# brush_driver.net
KiCad netlist of a schematic drawn in Altium Designer
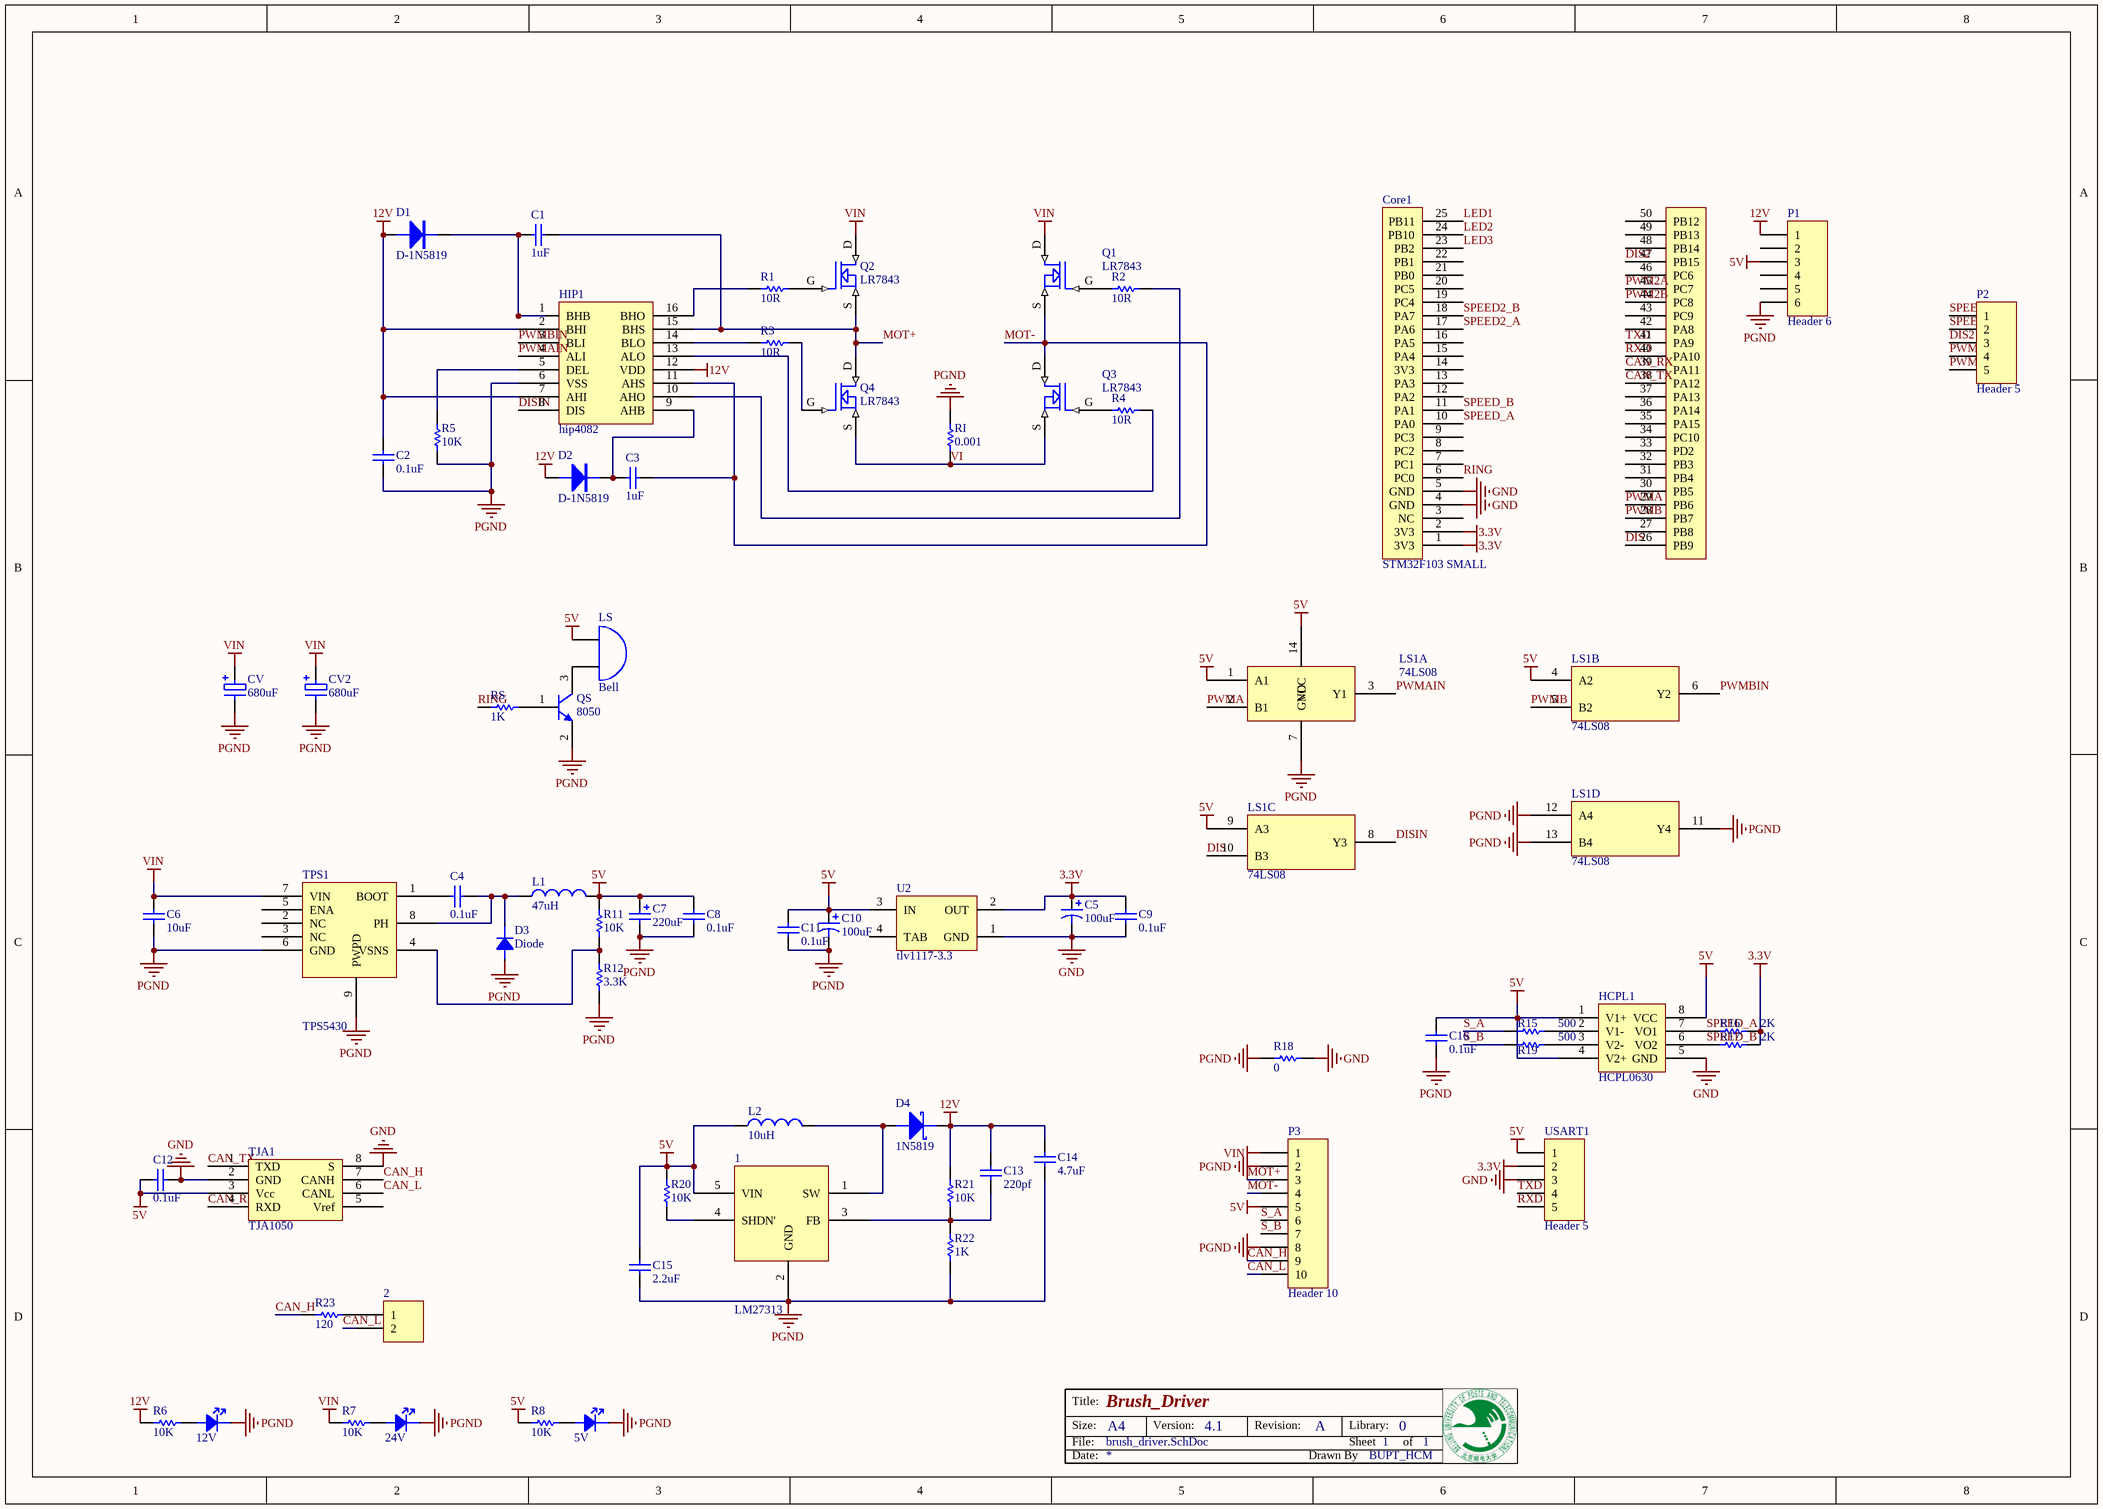
[diagram p0: brush_driver.SchDoc]

(export (version "E")
  (design (tool "Eeschema 10.0.6"))
  (components
    (comp (ref "1")
      (value "LM27313")
      (footprint "LM27313")
      (libsource (lib "K60-mainboard-v3.1") (part "LM27313"))
    )
    (comp (ref "2")
      (value "Header 2")
      (footprint "SIP2")
      (description "Header, 2-Pin")
      (fields (field (name "PUBLISHER") "Altium Limited"))
      (libsource (lib "Libraries_2014_0618") (part "Header 2"))
    )
    (comp (ref "5V")
      (value "lED")
      (footprint "0805D")
      (description "LED")
      (libsource (lib "K60-mainboard-v3.1") (part "00-D-LED"))
    )
    (comp (ref "12V")
      (value "lED")
      (footprint "0805D")
      (description "LED")
      (libsource (lib "K60-mainboard-v3.1") (part "00-D-LED"))
    )
    (comp (ref "24V")
      (value "lED")
      (footprint "0805D")
      (description "LED")
      (libsource (lib "K60-mainboard-v3.1") (part "00-D-LED"))
    )
    (comp (ref "C1")
      (value "1uF")
      (footprint "CAP-MLCC-0603")
      (description "Capacitor")
      (fields (field (name "Comment") "Cap") (field (name "PUBLISHER") "Altium Limited"))
      (libsource (lib "K60-mainboard-v3.1") (part "Cap"))
    )
    (comp (ref "C2")
      (value "0.1uF")
      (footprint "CAP-MLCC-0603")
      (description "Capacitor")
      (fields (field (name "Comment") "Cap") (field (name "PUBLISHER") "Altium Limited"))
      (libsource (lib "K60-mainboard-v3.1") (part "Cap"))
    )
    (comp (ref "C3")
      (value "1uF")
      (footprint "CAP-MLCC-0603")
      (description "Capacitor")
      (fields (field (name "Comment") "Cap") (field (name "PUBLISHER") "Altium Limited"))
      (libsource (lib "K60-mainboard-v3.1") (part "Cap"))
    )
    (comp (ref "C4")
      (value "0.1uF")
      (footprint "CAP-MLCC-0603")
      (description "Capacitor")
      (fields (field (name "Comment") "Cap") (field (name "PUBLISHER") "Altium Limited"))
      (libsource (lib "K60-mainboard-v3.1") (part "Cap"))
    )
    (comp (ref "C5")
      (value "100uF")
      (footprint "6032C")
      (description "Polarized Capacitor (Surface Mount)")
      (fields (field (name "Comment") "Cap Pol3") (field (name "PUBLISHER") "Altium Limited"))
      (libsource (lib "K60-mainboard-v3.1") (part "Cap Pol3"))
    )
    (comp (ref "C6")
      (value "10uF")
      (footprint "0805C")
      (description "Capacitor")
      (fields (field (name "Comment") "Cap") (field (name "PUBLISHER") "Altium Limited"))
      (libsource (lib "K60-mainboard-v3.1") (part "Cap"))
    )
    (comp (ref "C7")
      (value "220uF")
      (footprint "CAP-TAN-7343/CAPD")
      (description "Polarized Capacitor (Radial)")
      (fields (field (name "Comment") "Cap Pol1") (field (name "PUBLISHER") "Altium Limited"))
      (libsource (lib "K60-mainboard-v3.1") (part "Cap Pol1"))
    )
    (comp (ref "C8")
      (value "0.1uF")
      (footprint "CAP-MLCC-0603")
      (description "Capacitor")
      (fields (field (name "Comment") "Cap") (field (name "PUBLISHER") "Altium Limited"))
      (libsource (lib "K60-mainboard-v3.1") (part "Cap"))
    )
    (comp (ref "C9")
      (value "0.1uF")
      (footprint "CAP-MLCC-0603")
      (description "Capacitor")
      (fields (field (name "Comment") "Cap") (field (name "PUBLISHER") "Altium Limited"))
      (libsource (lib "K60-mainboard-v3.1") (part "Cap"))
    )
    (comp (ref "C10")
      (value "100uF")
      (footprint "6032C")
      (description "Polarized Capacitor (Surface Mount)")
      (fields (field (name "Comment") "Cap Pol3") (field (name "PUBLISHER") "Altium Limited"))
      (libsource (lib "K60-mainboard-v3.1") (part "Cap Pol3"))
    )
    (comp (ref "C11")
      (value "0.1uF")
      (footprint "CAP-MLCC-0603")
      (description "Capacitor")
      (fields (field (name "Comment") "Cap") (field (name "PUBLISHER") "Altium Limited"))
      (libsource (lib "K60-mainboard-v3.1") (part "Cap"))
    )
    (comp (ref "C12")
      (value "0.1uF")
      (footprint "CAP-MLCC-0603")
      (description "Capacitor")
      (fields (field (name "Comment") "Cap") (field (name "PUBLISHER") "Altium Limited"))
      (libsource (lib "K60-mainboard-v3.1") (part "Cap"))
    )
    (comp (ref "C13")
      (value "220pf")
      (footprint "CAP-MLCC-0603")
      (description "Capacitor")
      (fields (field (name "Comment") "Cap") (field (name "PUBLISHER") "Altium Limited"))
      (libsource (lib "K60-mainboard-v3.1") (part "Cap_1"))
    )
    (comp (ref "C14")
      (value "4.7uF")
      (footprint "CAP-MLCC-0603")
      (description "Capacitor")
      (fields (field (name "Comment") "Cap") (field (name "PUBLISHER") "Altium Limited"))
      (libsource (lib "K60-mainboard-v3.1") (part "Cap_1"))
    )
    (comp (ref "C15")
      (value "2.2uF")
      (footprint "CAP-MLCC-0603")
      (description "Capacitor")
      (fields (field (name "Comment") "Cap") (field (name "PUBLISHER") "Altium Limited"))
      (libsource (lib "K60-mainboard-v3.1") (part "Cap_1"))
    )
    (comp (ref "C16")
      (value "0.1uF")
      (footprint "CAP-MLCC-0603")
      (description "Capacitor")
      (fields (field (name "Comment") "Cap") (field (name "PUBLISHER") "Altium Limited"))
      (libsource (lib "K60-mainboard-v3.1") (part "Cap"))
    )
    (comp (ref "Core1")
      (value "STM32F103 SMALL")
      (footprint "STM32F103Small")
      (libsource (lib "K60-mainboard-v3.1") (part "STM32F103 SMALL"))
    )
    (comp (ref "CV")
      (value "680uF")
      (footprint "C_ELE")
      (description "电解电容")
      (fields (field (name "PUBLISHER") "Altium Limited"))
      (libsource (lib "Libraries_2014_0618") (part "CAP-ELE"))
    )
    (comp (ref "CV2")
      (value "680uF")
      (footprint "C_ELE")
      (description "电解电容")
      (fields (field (name "PUBLISHER") "Altium Limited"))
      (libsource (lib "Libraries_2014_0618") (part "CAP-ELE"))
    )
    (comp (ref "D1")
      (value "D-1N5819")
      (footprint "0805D")
      (description "Diode")
      (libsource (lib "常用器件") (part "D-1N5819"))
    )
    (comp (ref "D2")
      (value "D-1N5819")
      (footprint "0805D")
      (description "Diode")
      (libsource (lib "常用器件") (part "D-1N5819"))
    )
    (comp (ref "D3") (value "Diode") (footprint "SS34") (libsource (lib "K60-mainboard-v3.1") (part "Diode")))
    (comp (ref "D4")
      (value "1N5819")
      (footprint "0805D")
      (description "MBRA140T3")
      (libsource (lib "常用器件") (part "D-MBRA140T3"))
    )
    (comp (ref "HCPL1")
      (value "HCPL0630")
      (footprint "SOIC8")
      (libsource (lib "K60-mainboard-v3.1") (part "HCPL0630"))
    )
    (comp (ref "HIP1") (value "hip4082") (footprint "SOP16") (libsource (lib "元件库") (part "hip4082")))
    (comp (ref "L1")
      (value "47uH")
      (footprint "CD74")
      (description "Inductor")
      (fields (field (name "PUBLISHER") "Altium Limited"))
      (libsource (lib "smartcar_example") (part "Inductor"))
    )
    (comp (ref "L2")
      (value "10uH")
      (footprint "CD52")
      (description "Inductor")
      (fields (field (name "PUBLISHER") "Altium Limited"))
      (libsource (lib "smartcar_example") (part "Inductor"))
    )
    (comp (ref "LS")
      (value "Bell")
      (footprint "Ring")
      (description "Electrical Bell")
      (fields (field (name "PUBLISHER") "Altium Limited"))
      (libsource (lib "附加元件") (part "Bell"))
    )
    (comp (ref "LS1")
      (value "74LS08")
      (footprint "SOJ-14")
      (libsource (lib "K60-mainboard-v3.1") (part "74LS08"))
    )
    (comp (ref "P1")
      (value "Header 6")
      (footprint "HDR1X6")
      (description "Header, 6-Pin")
      (fields (field (name "PUBLISHER") "Altium Limited"))
      (libsource (lib "K60-mainboard-v3.1") (part "Header 6"))
    )
    (comp (ref "P2")
      (value "Header 5")
      (footprint "HDR1X5")
      (description "Header, 5-Pin")
      (fields (field (name "PUBLISHER") "Altium Limited"))
      (libsource (lib "K60-mainboard-v3.1") (part "Header 5"))
    )
    (comp (ref "P3")
      (value "Header 10")
      (footprint "Green 10P")
      (description "Header, 10-Pin")
      (fields (field (name "PUBLISHER") "Altium Limited"))
      (libsource (lib "Libraries_2014_0618") (part "Header 10"))
    )
    (comp (ref "Q1")
      (value "LR7843")
      (footprint "LR7843")
      (libsource (lib "K60-mainboard-v3.1") (part "LR7843"))
    )
    (comp (ref "Q2")
      (value "LR7843")
      (footprint "LR7843")
      (libsource (lib "K60-mainboard-v3.1") (part "LR7843"))
    )
    (comp (ref "Q3")
      (value "LR7843")
      (footprint "LR7843")
      (libsource (lib "K60-mainboard-v3.1") (part "LR7843"))
    )
    (comp (ref "Q4")
      (value "LR7843")
      (footprint "LR7843")
      (libsource (lib "K60-mainboard-v3.1") (part "LR7843"))
    )
    (comp (ref "QS")
      (value "8050")
      (footprint "SOT-23B_N")
      (description "NPN Bipolar Transistor")
      (fields (field (name "PUBLISHER") "Altium Limited"))
      (libsource (lib "附加元件") (part "QNPN"))
    )
    (comp (ref "R1")
      (value "10R")
      (footprint "RES-0603")
      (description "Resistor")
      (fields (field (name "Comment") "Res1") (field (name "PUBLISHER") "Altium Limited"))
      (libsource (lib "K60-mainboard-v3.1") (part "Res1"))
    )
    (comp (ref "R2")
      (value "10R")
      (footprint "RES-0603")
      (description "Resistor")
      (fields (field (name "Comment") "Res1") (field (name "PUBLISHER") "Altium Limited"))
      (libsource (lib "K60-mainboard-v3.1") (part "Res1"))
    )
    (comp (ref "R3")
      (value "10R")
      (footprint "RES-0603")
      (description "Resistor")
      (fields (field (name "Comment") "Res1") (field (name "PUBLISHER") "Altium Limited"))
      (libsource (lib "K60-mainboard-v3.1") (part "Res1"))
    )
    (comp (ref "R4")
      (value "10R")
      (footprint "RES-0603")
      (description "Resistor")
      (fields (field (name "Comment") "Res1") (field (name "PUBLISHER") "Altium Limited"))
      (libsource (lib "K60-mainboard-v3.1") (part "Res1"))
    )
    (comp (ref "R5")
      (value "10K")
      (footprint "RES-0603")
      (description "Resistor")
      (fields (field (name "Comment") "Res1") (field (name "PUBLISHER") "Altium Limited"))
      (libsource (lib "K60-mainboard-v3.1") (part "Res1"))
    )
    (comp (ref "R6")
      (value "10K")
      (footprint "RES-0603")
      (description "Resistor")
      (fields (field (name "Comment") "Res1") (field (name "PUBLISHER") "Altium Limited"))
      (libsource (lib "K60-mainboard-v3.1") (part "Res1"))
    )
    (comp (ref "R7")
      (value "10K")
      (footprint "RES-0603")
      (description "Resistor")
      (fields (field (name "Comment") "Res1") (field (name "PUBLISHER") "Altium Limited"))
      (libsource (lib "K60-mainboard-v3.1") (part "Res1"))
    )
    (comp (ref "R8")
      (value "10K")
      (footprint "RES-0603")
      (description "Resistor")
      (fields (field (name "Comment") "Res1") (field (name "PUBLISHER") "Altium Limited"))
      (libsource (lib "K60-mainboard-v3.1") (part "Res1"))
    )
    (comp (ref "R11")
      (value "10K")
      (footprint "RES-0603")
      (description "Resistor")
      (fields (field (name "Comment") "Res1") (field (name "PUBLISHER") "Altium Limited"))
      (libsource (lib "K60-mainboard-v3.1") (part "Res1"))
    )
    (comp (ref "R12")
      (value "3.3K")
      (footprint "RES-0603")
      (description "Resistor")
      (fields (field (name "Comment") "Res1") (field (name "PUBLISHER") "Altium Limited"))
      (libsource (lib "K60-mainboard-v3.1") (part "Res1"))
    )
    (comp (ref "R15")
      (value "500")
      (footprint "RES-0603")
      (description "Resistor")
      (fields (field (name "Comment") "Res1") (field (name "PUBLISHER") "Altium Limited"))
      (libsource (lib "K60-mainboard-v3.1") (part "Res1"))
    )
    (comp (ref "R16")
      (value "2K")
      (footprint "RES-0603")
      (description "Resistor")
      (fields (field (name "Comment") "Res1") (field (name "PUBLISHER") "Altium Limited"))
      (libsource (lib "K60-mainboard-v3.1") (part "Res1"))
    )
    (comp (ref "R17")
      (value "2K")
      (footprint "RES-0603")
      (description "Resistor")
      (fields (field (name "Comment") "Res1") (field (name "PUBLISHER") "Altium Limited"))
      (libsource (lib "K60-mainboard-v3.1") (part "Res1"))
    )
    (comp (ref "R18")
      (value "0")
      (footprint "RES-0603")
      (description "Resistor")
      (fields (field (name "Comment") "Res1") (field (name "PUBLISHER") "Altium Limited"))
      (libsource (lib "K60-mainboard-v3.1") (part "Res1"))
    )
    (comp (ref "R19")
      (value "500")
      (footprint "RES-0603")
      (description "Resistor")
      (fields (field (name "Comment") "Res1") (field (name "PUBLISHER") "Altium Limited"))
      (libsource (lib "K60-mainboard-v3.1") (part "Res1"))
    )
    (comp (ref "R20")
      (value "10K")
      (footprint "RES-0603")
      (description "Resistor")
      (fields (field (name "Comment") "Res1") (field (name "PUBLISHER") "Altium Limited"))
      (libsource (lib "K60-mainboard-v3.1") (part "Res1_1"))
    )
    (comp (ref "R21")
      (value "10K")
      (footprint "RES-0603")
      (description "Resistor")
      (fields (field (name "Comment") "Res1") (field (name "PUBLISHER") "Altium Limited"))
      (libsource (lib "K60-mainboard-v3.1") (part "Res1_1"))
    )
    (comp (ref "R22")
      (value "1K")
      (footprint "RES-0603")
      (description "Resistor")
      (fields (field (name "Comment") "Res1") (field (name "PUBLISHER") "Altium Limited"))
      (libsource (lib "K60-mainboard-v3.1") (part "Res1_1"))
    )
    (comp (ref "R23")
      (value "120")
      (footprint "RES-0603")
      (description "Resistor")
      (fields (field (name "Comment") "Res1") (field (name "PUBLISHER") "Altium Limited"))
      (libsource (lib "K60-mainboard-v3.1") (part "Res1"))
    )
    (comp (ref "RI")
      (value "0.001")
      (footprint "2512R")
      (description "Resistor")
      (fields (field (name "Comment") "Res1") (field (name "PUBLISHER") "Altium Limited"))
      (libsource (lib "K60-mainboard-v3.1") (part "Res1"))
    )
    (comp (ref "RS")
      (value "1K")
      (footprint "RES-0603")
      (description "Resistor")
      (fields (field (name "Comment") "Res1") (field (name "PUBLISHER") "Altium Limited"))
      (libsource (lib "K60-mainboard-v3.1") (part "Res1"))
    )
    (comp (ref "TJA1")
      (value "TJA1050")
      (footprint "TJA1050")
      (description "CAN总线收发器")
      (libsource (lib "Libraries_2014_0618") (part "TJA1050"))
    )
    (comp (ref "TPS1")
      (value "TPS5430")
      (footprint "TPS5430")
      (libsource (lib "K60-mainboard-v3.1") (part "TPS5430"))
    )
    (comp (ref "U2")
      (value "tlv1117-3.3")
      (footprint "LM1117")
      (description "800mA Low-Dropout Linear Regulator")
      (fields
        (field (name "PARTNUMBER") "LM1117IMP-5.0")
        (field (name "MANUFACTURER") "National Semiconductor")
        (field (name "PUBLISHER") "Altium Limited")
      )
      (libsource (lib "K60-mainboard-v3.1") (part "LM1117IMP-5.0"))
    )
    (comp (ref "USART1")
      (value "Header 5")
      (footprint "Green_5P")
      (description "Header, 5-Pin")
      (fields (field (name "PUBLISHER") "Altium Limited"))
      (libsource (lib "Libraries_2014_0618") (part "Header 5"))
    )
  )
  (nets
    (net (code "1") (name "/CAN_H") (class "Default")
      (node (ref "P3") (pin "9") (pinfunction "9_9") (pintype "passive"))
      (node (ref "R23") (pin "2") (pinfunction "2_2") (pintype "passive"))
      (node (ref "TJA1") (pin "7") (pinfunction "CANH_7") (pintype "passive"))
    )
    (net (code "2") (name "/CAN_L") (class "Default")
      (node (ref "2") (pin "2") (pinfunction "2_2") (pintype "passive"))
      (node (ref "P3") (pin "10") (pinfunction "10_10") (pintype "passive"))
      (node (ref "TJA1") (pin "6") (pinfunction "CANL_6") (pintype "passive"))
    )
    (net (code "3") (name "/CAN_RX") (class "Default")
      (node (ref "Core1") (pin "39") (pinfunction "PA11_39") (pintype "passive"))
      (node (ref "TJA1") (pin "4") (pinfunction "RXD_4") (pintype "passive"))
    )
    (net (code "4") (name "/CAN_TX") (class "Default")
      (node (ref "Core1") (pin "38") (pinfunction "PA12_38") (pintype "passive"))
      (node (ref "TJA1") (pin "1") (pinfunction "TXD_1") (pintype "passive"))
    )
    (net (code "5") (name "/DIS") (class "Default")
      (node (ref "Core1") (pin "26") (pinfunction "PB9_26") (pintype "passive"))
      (node (ref "LS1") (pin "10") (pinfunction "B3_10") (pintype "passive"))
    )
    (net (code "6") (name "/DIS2") (class "Default")
      (node (ref "Core1") (pin "47") (pinfunction "PB15_47") (pintype "passive"))
      (node (ref "P2") (pin "3") (pinfunction "3_3") (pintype "passive"))
    )
    (net (code "7") (name "/DISIN") (class "Default")
      (node (ref "HIP1") (pin "8") (pinfunction "DIS_8") (pintype "passive"))
      (node (ref "LS1") (pin "8") (pinfunction "Y3_8") (pintype "passive"))
    )
    (net (code "8") (name "/LED1") (class "Default")
      (node (ref "Core1") (pin "25") (pinfunction "PB11_25") (pintype "passive"))
    )
    (net (code "9") (name "/LED2") (class "Default")
      (node (ref "Core1") (pin "24") (pinfunction "PB10_24") (pintype "passive"))
    )
    (net (code "10") (name "/LED3") (class "Default")
      (node (ref "Core1") (pin "23") (pinfunction "PB2_23") (pintype "passive"))
    )
    (net (code "11") (name "/MOT+") (class "Default")
      (node (ref "C1") (pin "1") (pinfunction "1_1") (pintype "passive"))
      (node (ref "HIP1") (pin "15") (pinfunction "BHS_15") (pintype "passive"))
      (node (ref "P3") (pin "3") (pinfunction "3_3") (pintype "passive"))
      (node (ref "Q2") (pin "S") (pinfunction "S_S") (pintype "input"))
      (node (ref "Q4") (pin "D") (pinfunction "D_D") (pintype "input"))
    )
    (net (code "12") (name "/MOT-") (class "Default")
      (node (ref "C3") (pin "1") (pinfunction "1_1") (pintype "passive"))
      (node (ref "HIP1") (pin "11") (pinfunction "AHS_11") (pintype "passive"))
      (node (ref "P3") (pin "4") (pinfunction "4_4") (pintype "passive"))
      (node (ref "Q1") (pin "S") (pinfunction "S_S") (pintype "input"))
      (node (ref "Q3") (pin "D") (pinfunction "D_D") (pintype "input"))
    )
    (net (code "13") (name "/PWM2A") (class "Default")
      (node (ref "Core1") (pin "45") (pinfunction "PC7_45") (pintype "passive"))
      (node (ref "P2") (pin "4") (pinfunction "4_4") (pintype "passive"))
    )
    (net (code "14") (name "/PWM2B") (class "Default")
      (node (ref "Core1") (pin "44") (pinfunction "PC8_44") (pintype "passive"))
      (node (ref "P2") (pin "5") (pinfunction "5_5") (pintype "passive"))
    )
    (net (code "15") (name "/PWMA") (class "Default")
      (node (ref "Core1") (pin "29") (pinfunction "PB6_29") (pintype "passive"))
      (node (ref "LS1") (pin "2") (pinfunction "B1_2") (pintype "passive"))
    )
    (net (code "16") (name "/PWMAIN") (class "Default")
      (node (ref "HIP1") (pin "4") (pinfunction "ALI_4") (pintype "passive"))
      (node (ref "LS1") (pin "3") (pinfunction "Y1_3") (pintype "passive"))
    )
    (net (code "17") (name "/PWMB") (class "Default")
      (node (ref "Core1") (pin "28") (pinfunction "PB7_28") (pintype "passive"))
      (node (ref "LS1") (pin "5") (pinfunction "B2_5") (pintype "passive"))
    )
    (net (code "18") (name "/PWMBIN") (class "Default")
      (node (ref "HIP1") (pin "3") (pinfunction "BLI_3") (pintype "passive"))
      (node (ref "LS1") (pin "6") (pinfunction "Y2_6") (pintype "passive"))
    )
    (net (code "19") (name "/RING") (class "Default")
      (node (ref "Core1") (pin "6") (pinfunction "PC0_6") (pintype "passive"))
      (node (ref "RS") (pin "2") (pinfunction "2_2") (pintype "passive"))
    )
    (net (code "20") (name "/RXD") (class "Default")
      (node (ref "Core1") (pin "40") (pinfunction "PA10_40") (pintype "passive"))
      (node (ref "USART1") (pin "5") (pinfunction "5_5") (pintype "passive"))
    )
    (net (code "21") (name "/SPEED2_A") (class "Default")
      (node (ref "Core1") (pin "17") (pinfunction "PA6_17") (pintype "passive"))
      (node (ref "P2") (pin "2") (pinfunction "2_2") (pintype "passive"))
    )
    (net (code "22") (name "/SPEED2_B") (class "Default")
      (node (ref "Core1") (pin "18") (pinfunction "PA7_18") (pintype "passive"))
      (node (ref "P2") (pin "1") (pinfunction "1_1") (pintype "passive"))
    )
    (net (code "23") (name "/SPEED_A") (class "Default")
      (node (ref "Core1") (pin "10") (pinfunction "PA0_10") (pintype "passive"))
      (node (ref "HCPL1") (pin "7") (pinfunction "VO1_7") (pintype "passive"))
      (node (ref "R16") (pin "1") (pinfunction "1_1") (pintype "passive"))
    )
    (net (code "24") (name "/SPEED_B") (class "Default")
      (node (ref "Core1") (pin "11") (pinfunction "PA1_11") (pintype "passive"))
      (node (ref "HCPL1") (pin "6") (pinfunction "VO2_6") (pintype "passive"))
      (node (ref "R17") (pin "1") (pinfunction "1_1") (pintype "passive"))
    )
    (net (code "25") (name "/S_A") (class "Default")
      (node (ref "P3") (pin "6") (pinfunction "6_6") (pintype "passive"))
      (node (ref "R15") (pin "1") (pinfunction "1_1") (pintype "passive"))
    )
    (net (code "26") (name "/S_B") (class "Default")
      (node (ref "P3") (pin "7") (pinfunction "7_7") (pintype "passive"))
      (node (ref "R19") (pin "1") (pinfunction "1_1") (pintype "passive"))
    )
    (net (code "27") (name "/TXD") (class "Default")
      (node (ref "Core1") (pin "41") (pinfunction "PA9_41") (pintype "passive"))
      (node (ref "USART1") (pin "4") (pinfunction "4_4") (pintype "passive"))
    )
    (net (code "28") (name "/VI") (class "Default")
      (node (ref "Q3") (pin "S") (pinfunction "S_S") (pintype "input"))
      (node (ref "Q4") (pin "S") (pinfunction "S_S") (pintype "input"))
      (node (ref "RI") (pin "1") (pinfunction "1_1") (pintype "passive"))
    )
    (net (code "29") (name "3.3V") (class "Default")
      (node (ref "C5") (pin "1") (pinfunction "1_1") (pintype "passive"))
      (node (ref "C9") (pin "1") (pinfunction "1_1") (pintype "passive"))
      (node (ref "Core1") (pin "1") (pinfunction "3V3_1") (pintype "passive"))
      (node (ref "Core1") (pin "2") (pinfunction "3V3_2") (pintype "passive"))
      (node (ref "R16") (pin "2") (pinfunction "2_2") (pintype "passive"))
      (node (ref "R17") (pin "2") (pinfunction "2_2") (pintype "passive"))
      (node (ref "U2") (pin "2") (pinfunction "OUT_2") (pintype "power_in"))
      (node (ref "USART1") (pin "2") (pinfunction "2_2") (pintype "passive"))
    )
    (net (code "30") (name "5V") (class "Default")
      (node (ref "1") (pin "5") (pinfunction "VIN_5") (pintype "passive"))
      (node (ref "C10") (pin "1") (pinfunction "1_1") (pintype "passive"))
      (node (ref "C11") (pin "1") (pinfunction "1_1") (pintype "passive"))
      (node (ref "C12") (pin "1") (pinfunction "1_1") (pintype "passive"))
      (node (ref "C15") (pin "2") (pinfunction "2_2") (pintype "passive"))
      (node (ref "C16") (pin "1") (pinfunction "1_1") (pintype "passive"))
      (node (ref "C7") (pin "1") (pinfunction "1_1") (pintype "passive"))
      (node (ref "C8") (pin "2") (pinfunction "2_2") (pintype "passive"))
      (node (ref "HCPL1") (pin "1") (pinfunction "V1+_1") (pintype "passive"))
      (node (ref "HCPL1") (pin "4") (pinfunction "V2+_4") (pintype "passive"))
      (node (ref "HCPL1") (pin "8") (pinfunction "VCC_8") (pintype "passive"))
      (node (ref "L1") (pin "2") (pinfunction "2_2") (pintype "passive"))
      (node (ref "L2") (pin "1") (pinfunction "1_1") (pintype "passive"))
      (node (ref "LS") (pin "1") (pinfunction "A_1") (pintype "passive"))
      (node (ref "LS1") (pin "1") (pinfunction "A1_1") (pintype "passive"))
      (node (ref "LS1") (pin "14") (pinfunction "VCC_14") (pintype "passive"))
      (node (ref "LS1") (pin "4") (pinfunction "A2_4") (pintype "passive"))
      (node (ref "LS1") (pin "9") (pinfunction "A3_9") (pintype "passive"))
      (node (ref "P1") (pin "3") (pinfunction "3_3") (pintype "passive"))
      (node (ref "P3") (pin "5") (pinfunction "5_5") (pintype "passive"))
      (node (ref "R11") (pin "2") (pinfunction "2_2") (pintype "passive"))
      (node (ref "R20") (pin "1") (pinfunction "1_1") (pintype "passive"))
      (node (ref "R8") (pin "2") (pinfunction "2_2") (pintype "passive"))
      (node (ref "TJA1") (pin "3") (pinfunction "Vcc_3") (pintype "passive"))
      (node (ref "U2") (pin "3") (pinfunction "IN_3") (pintype "power_in"))
      (node (ref "USART1") (pin "1") (pinfunction "1_1") (pintype "passive"))
    )
    (net (code "31") (name "12V") (class "Default")
      (node (ref "C13") (pin "2") (pinfunction "2_2") (pintype "passive"))
      (node (ref "C14") (pin "2") (pinfunction "2_2") (pintype "passive"))
      (node (ref "C2") (pin "2") (pinfunction "2_2") (pintype "passive"))
      (node (ref "D1") (pin "A") (pinfunction "1_A") (pintype "passive"))
      (node (ref "D2") (pin "A") (pinfunction "1_A") (pintype "passive"))
      (node (ref "D4") (pin "K") (pinfunction "2_K") (pintype "passive"))
      (node (ref "HIP1") (pin "12") (pinfunction "VDD_12") (pintype "passive"))
      (node (ref "HIP1") (pin "2") (pinfunction "BHI_2") (pintype "passive"))
      (node (ref "HIP1") (pin "7") (pinfunction "AHI_7") (pintype "passive"))
      (node (ref "P1") (pin "1") (pinfunction "1_1") (pintype "passive"))
      (node (ref "R21") (pin "1") (pinfunction "1_1") (pintype "passive"))
      (node (ref "R6") (pin "2") (pinfunction "2_2") (pintype "passive"))
    )
    (net (code "32") (name "GND") (class "Default")
      (node (ref "C12") (pin "2") (pinfunction "2_2") (pintype "passive"))
      (node (ref "C5") (pin "2") (pinfunction "2_2") (pintype "passive"))
      (node (ref "C9") (pin "2") (pinfunction "2_2") (pintype "passive"))
      (node (ref "Core1") (pin "4") (pinfunction "GND_4") (pintype "passive"))
      (node (ref "Core1") (pin "5") (pinfunction "GND_5") (pintype "passive"))
      (node (ref "HCPL1") (pin "5") (pinfunction "GND_5") (pintype "passive"))
      (node (ref "R18") (pin "2") (pinfunction "2_2") (pintype "passive"))
      (node (ref "TJA1") (pin "2") (pinfunction "GND_2") (pintype "passive"))
      (node (ref "TJA1") (pin "8") (pinfunction "S_8") (pintype "passive"))
      (node (ref "U2") (pin "1") (pinfunction "GND_1") (pintype "power_in"))
      (node (ref "USART1") (pin "3") (pinfunction "3_3") (pintype "passive"))
    )
    (net (code "33") (name "Net-(1-FB)") (class "Default")
      (node (ref "1") (pin "3") (pinfunction "FB_3") (pintype "passive"))
      (node (ref "C13") (pin "1") (pinfunction "1_1") (pintype "passive"))
      (node (ref "R21") (pin "2") (pinfunction "2_2") (pintype "passive"))
      (node (ref "R22") (pin "1") (pinfunction "1_1") (pintype "passive"))
    )
    (net (code "34") (name "Net-(1-SHDN')") (class "Default")
      (node (ref "1") (pin "4") (pinfunction "SHDN'_4") (pintype "passive"))
      (node (ref "R20") (pin "2") (pinfunction "2_2") (pintype "passive"))
    )
    (net (code "35") (name "Net-(1-SW)") (class "Default")
      (node (ref "1") (pin "1") (pinfunction "SW_1") (pintype "passive"))
      (node (ref "D4") (pin "A") (pinfunction "1_A") (pintype "passive"))
      (node (ref "L2") (pin "2") (pinfunction "2_2") (pintype "passive"))
    )
    (net (code "36") (name "Net-(2-Pad1)") (class "Default")
      (node (ref "2") (pin "1") (pinfunction "1_1") (pintype "passive"))
      (node (ref "R23") (pin "1") (pinfunction "1_1") (pintype "passive"))
    )
    (net (code "37") (name "Net-(5V-1)") (class "Default")
      (node (ref "5V") (pin "A") (pinfunction "1_A") (pintype "passive"))
      (node (ref "R8") (pin "1") (pinfunction "1_1") (pintype "passive"))
    )
    (net (code "38") (name "Net-(12V-1)") (class "Default")
      (node (ref "12V") (pin "A") (pinfunction "1_A") (pintype "passive"))
      (node (ref "R6") (pin "1") (pinfunction "1_1") (pintype "passive"))
    )
    (net (code "39") (name "Net-(24V-1)") (class "Default")
      (node (ref "24V") (pin "A") (pinfunction "1_A") (pintype "passive"))
      (node (ref "R7") (pin "1") (pinfunction "1_1") (pintype "passive"))
    )
    (net (code "40") (name "Net-(D1-2)") (class "Default")
      (node (ref "C1") (pin "2") (pinfunction "2_2") (pintype "passive"))
      (node (ref "D1") (pin "K") (pinfunction "2_K") (pintype "passive"))
      (node (ref "HIP1") (pin "1") (pinfunction "BHB_1") (pintype "passive"))
    )
    (net (code "41") (name "Net-(D2-2)") (class "Default")
      (node (ref "C3") (pin "2") (pinfunction "2_2") (pintype "passive"))
      (node (ref "D2") (pin "K") (pinfunction "2_K") (pintype "passive"))
      (node (ref "HIP1") (pin "9") (pinfunction "AHB_9") (pintype "passive"))
    )
    (net (code "42") (name "Net-(D3-2)") (class "Default")
      (node (ref "C4") (pin "2") (pinfunction "2_2") (pintype "passive"))
      (node (ref "D3") (pin "K") (pinfunction "2_K") (pintype "passive"))
      (node (ref "L1") (pin "1") (pinfunction "1_1") (pintype "passive"))
      (node (ref "TPS1") (pin "8") (pinfunction "PH_8") (pintype "passive"))
    )
    (net (code "43") (name "Net-(HCPL1-V1-)") (class "Default")
      (node (ref "HCPL1") (pin "2") (pinfunction "V1-_2") (pintype "passive"))
      (node (ref "R15") (pin "2") (pinfunction "2_2") (pintype "passive"))
    )
    (net (code "44") (name "Net-(HCPL1-V2-)") (class "Default")
      (node (ref "HCPL1") (pin "3") (pinfunction "V2-_3") (pintype "passive"))
      (node (ref "R19") (pin "2") (pinfunction "2_2") (pintype "passive"))
    )
    (net (code "45") (name "Net-(HIP1-AHO)") (class "Default")
      (node (ref "HIP1") (pin "10") (pinfunction "AHO_10") (pintype "passive"))
      (node (ref "R2") (pin "2") (pinfunction "2_2") (pintype "passive"))
    )
    (net (code "46") (name "Net-(HIP1-ALO)") (class "Default")
      (node (ref "HIP1") (pin "13") (pinfunction "ALO_13") (pintype "passive"))
      (node (ref "R4") (pin "2") (pinfunction "2_2") (pintype "passive"))
    )
    (net (code "47") (name "Net-(HIP1-BHO)") (class "Default")
      (node (ref "HIP1") (pin "16") (pinfunction "BHO_16") (pintype "passive"))
      (node (ref "R1") (pin "2") (pinfunction "2_2") (pintype "passive"))
    )
    (net (code "48") (name "Net-(HIP1-BLO)") (class "Default")
      (node (ref "HIP1") (pin "14") (pinfunction "BLO_14") (pintype "passive"))
      (node (ref "R3") (pin "1") (pinfunction "1_1") (pintype "passive"))
    )
    (net (code "49") (name "Net-(HIP1-DEL)") (class "Default")
      (node (ref "HIP1") (pin "5") (pinfunction "DEL_5") (pintype "passive"))
      (node (ref "R5") (pin "2") (pinfunction "2_2") (pintype "passive"))
    )
    (net (code "50") (name "Net-(LS-B)") (class "Default")
      (node (ref "LS") (pin "2") (pinfunction "B_2") (pintype "passive"))
      (node (ref "QS") (pin "3") (pinfunction "C_3") (pintype "passive"))
    )
    (net (code "51") (name "Net-(Q1-PadG)") (class "Default")
      (node (ref "Q1") (pin "G") (pinfunction "G_G") (pintype "input"))
      (node (ref "R2") (pin "1") (pinfunction "1_1") (pintype "passive"))
    )
    (net (code "52") (name "Net-(Q2-PadG)") (class "Default")
      (node (ref "Q2") (pin "G") (pinfunction "G_G") (pintype "input"))
      (node (ref "R1") (pin "1") (pinfunction "1_1") (pintype "passive"))
    )
    (net (code "53") (name "Net-(Q3-PadG)") (class "Default")
      (node (ref "Q3") (pin "G") (pinfunction "G_G") (pintype "input"))
      (node (ref "R4") (pin "1") (pinfunction "1_1") (pintype "passive"))
    )
    (net (code "54") (name "Net-(Q4-PadG)") (class "Default")
      (node (ref "Q4") (pin "G") (pinfunction "G_G") (pintype "input"))
      (node (ref "R3") (pin "2") (pinfunction "2_2") (pintype "passive"))
    )
    (net (code "55") (name "Net-(QS-B)") (class "Default")
      (node (ref "QS") (pin "1") (pinfunction "B_1") (pintype "passive"))
      (node (ref "RS") (pin "1") (pinfunction "1_1") (pintype "passive"))
    )
    (net (code "56") (name "Net-(TPS1-BOOT)") (class "Default")
      (node (ref "C4") (pin "1") (pinfunction "1_1") (pintype "passive"))
      (node (ref "TPS1") (pin "1") (pinfunction "BOOT_1") (pintype "passive"))
    )
    (net (code "57") (name "Net-(TPS1-VSNS)") (class "Default")
      (node (ref "R11") (pin "1") (pinfunction "1_1") (pintype "passive"))
      (node (ref "R12") (pin "2") (pinfunction "2_2") (pintype "passive"))
      (node (ref "TPS1") (pin "4") (pinfunction "VSNS_4") (pintype "passive"))
    )
    (net (code "58") (name "PGND") (class "Default")
      (node (ref "1") (pin "2") (pinfunction "GND_2") (pintype "passive"))
      (node (ref "12V") (pin "K") (pinfunction "2_K") (pintype "passive"))
      (node (ref "24V") (pin "K") (pinfunction "2_K") (pintype "passive"))
      (node (ref "5V") (pin "K") (pinfunction "2_K") (pintype "passive"))
      (node (ref "C10") (pin "2") (pinfunction "2_2") (pintype "passive"))
      (node (ref "C11") (pin "2") (pinfunction "2_2") (pintype "passive"))
      (node (ref "C14") (pin "1") (pinfunction "1_1") (pintype "passive"))
      (node (ref "C15") (pin "1") (pinfunction "1_1") (pintype "passive"))
      (node (ref "C16") (pin "2") (pinfunction "2_2") (pintype "passive"))
      (node (ref "C2") (pin "1") (pinfunction "1_1") (pintype "passive"))
      (node (ref "C6") (pin "1") (pinfunction "1_1") (pintype "passive"))
      (node (ref "C7") (pin "2") (pinfunction "2_2") (pintype "passive"))
      (node (ref "C8") (pin "1") (pinfunction "1_1") (pintype "passive"))
      (node (ref "CV") (pin "2") (pinfunction "2_2") (pintype "passive"))
      (node (ref "CV2") (pin "2") (pinfunction "2_2") (pintype "passive"))
      (node (ref "D3") (pin "A") (pinfunction "1_A") (pintype "passive"))
      (node (ref "HIP1") (pin "6") (pinfunction "VSS_6") (pintype "passive"))
      (node (ref "LS1") (pin "11") (pinfunction "Y4_11") (pintype "passive"))
      (node (ref "LS1") (pin "12") (pinfunction "A4_12") (pintype "passive"))
      (node (ref "LS1") (pin "13") (pinfunction "B4_13") (pintype "passive"))
      (node (ref "LS1") (pin "7") (pinfunction "GND_7") (pintype "passive"))
      (node (ref "P1") (pin "6") (pinfunction "6_6") (pintype "passive"))
      (node (ref "P3") (pin "2") (pinfunction "2_2") (pintype "passive"))
      (node (ref "P3") (pin "8") (pinfunction "8_8") (pintype "passive"))
      (node (ref "QS") (pin "2") (pinfunction "E_2") (pintype "passive"))
      (node (ref "R12") (pin "1") (pinfunction "1_1") (pintype "passive"))
      (node (ref "R18") (pin "1") (pinfunction "1_1") (pintype "passive"))
      (node (ref "R22") (pin "2") (pinfunction "2_2") (pintype "passive"))
      (node (ref "R5") (pin "1") (pinfunction "1_1") (pintype "passive"))
      (node (ref "RI") (pin "2") (pinfunction "2_2") (pintype "passive"))
      (node (ref "TPS1") (pin "6") (pinfunction "GND_6") (pintype "passive"))
      (node (ref "TPS1") (pin "9") (pinfunction "PWPD_9") (pintype "passive"))
    )
    (net (code "59") (name "VIN") (class "Default")
      (node (ref "C6") (pin "2") (pinfunction "2_2") (pintype "passive"))
      (node (ref "CV") (pin "1") (pinfunction "1_1") (pintype "passive"))
      (node (ref "CV2") (pin "1") (pinfunction "1_1") (pintype "passive"))
      (node (ref "P3") (pin "1") (pinfunction "1_1") (pintype "passive"))
      (node (ref "Q1") (pin "D") (pinfunction "D_D") (pintype "input"))
      (node (ref "Q2") (pin "D") (pinfunction "D_D") (pintype "input"))
      (node (ref "R7") (pin "2") (pinfunction "2_2") (pintype "passive"))
      (node (ref "TPS1") (pin "7") (pinfunction "VIN_7") (pintype "passive"))
    )
    (net (code "60") (name "unconnected-(Core1-3V3-Pad14)") (class "Default")
      (node (ref "Core1") (pin "14") (pinfunction "3V3_14") (pintype "passive"))
    )
    (net (code "61") (name "unconnected-(Core1-NC-Pad3)") (class "Default")
      (node (ref "Core1") (pin "3") (pinfunction "NC_3") (pintype "passive"))
    )
    (net (code "62") (name "unconnected-(Core1-PA2-Pad12)") (class "Default")
      (node (ref "Core1") (pin "12") (pinfunction "PA2_12") (pintype "passive"))
    )
    (net (code "63") (name "unconnected-(Core1-PA3-Pad13)") (class "Default")
      (node (ref "Core1") (pin "13") (pinfunction "PA3_13") (pintype "passive"))
    )
    (net (code "64") (name "unconnected-(Core1-PA4-Pad15)") (class "Default")
      (node (ref "Core1") (pin "15") (pinfunction "PA4_15") (pintype "passive"))
    )
    (net (code "65") (name "unconnected-(Core1-PA5-Pad16)") (class "Default")
      (node (ref "Core1") (pin "16") (pinfunction "PA5_16") (pintype "passive"))
    )
    (net (code "66") (name "unconnected-(Core1-PA8-Pad42)") (class "Default")
      (node (ref "Core1") (pin "42") (pinfunction "PA8_42") (pintype "passive"))
    )
    (net (code "67") (name "unconnected-(Core1-PA13-Pad37)") (class "Default")
      (node (ref "Core1") (pin "37") (pinfunction "PA13_37") (pintype "passive"))
    )
    (net (code "68") (name "unconnected-(Core1-PA14-Pad36)") (class "Default")
      (node (ref "Core1") (pin "36") (pinfunction "PA14_36") (pintype "passive"))
    )
    (net (code "69") (name "unconnected-(Core1-PA15-Pad35)") (class "Default")
      (node (ref "Core1") (pin "35") (pinfunction "PA15_35") (pintype "passive"))
    )
    (net (code "70") (name "unconnected-(Core1-PB0-Pad21)") (class "Default")
      (node (ref "Core1") (pin "21") (pinfunction "PB0_21") (pintype "passive"))
    )
    (net (code "71") (name "unconnected-(Core1-PB1-Pad22)") (class "Default")
      (node (ref "Core1") (pin "22") (pinfunction "PB1_22") (pintype "passive"))
    )
    (net (code "72") (name "unconnected-(Core1-PB3-Pad32)") (class "Default")
      (node (ref "Core1") (pin "32") (pinfunction "PB3_32") (pintype "passive"))
    )
    (net (code "73") (name "unconnected-(Core1-PB4-Pad31)") (class "Default")
      (node (ref "Core1") (pin "31") (pinfunction "PB4_31") (pintype "passive"))
    )
    (net (code "74") (name "unconnected-(Core1-PB5-Pad30)") (class "Default")
      (node (ref "Core1") (pin "30") (pinfunction "PB5_30") (pintype "passive"))
    )
    (net (code "75") (name "unconnected-(Core1-PB8-Pad27)") (class "Default")
      (node (ref "Core1") (pin "27") (pinfunction "PB8_27") (pintype "passive"))
    )
    (net (code "76") (name "unconnected-(Core1-PB12-Pad50)") (class "Default")
      (node (ref "Core1") (pin "50") (pinfunction "PB12_50") (pintype "passive"))
    )
    (net (code "77") (name "unconnected-(Core1-PB13-Pad49)") (class "Default")
      (node (ref "Core1") (pin "49") (pinfunction "PB13_49") (pintype "passive"))
    )
    (net (code "78") (name "unconnected-(Core1-PB14-Pad48)") (class "Default")
      (node (ref "Core1") (pin "48") (pinfunction "PB14_48") (pintype "passive"))
    )
    (net (code "79") (name "unconnected-(Core1-PC1-Pad7)") (class "Default")
      (node (ref "Core1") (pin "7") (pinfunction "PC1_7") (pintype "passive"))
    )
    (net (code "80") (name "unconnected-(Core1-PC2-Pad8)") (class "Default")
      (node (ref "Core1") (pin "8") (pinfunction "PC2_8") (pintype "passive"))
    )
    (net (code "81") (name "unconnected-(Core1-PC3-Pad9)") (class "Default")
      (node (ref "Core1") (pin "9") (pinfunction "PC3_9") (pintype "passive"))
    )
    (net (code "82") (name "unconnected-(Core1-PC4-Pad19)") (class "Default")
      (node (ref "Core1") (pin "19") (pinfunction "PC4_19") (pintype "passive"))
    )
    (net (code "83") (name "unconnected-(Core1-PC5-Pad20)") (class "Default")
      (node (ref "Core1") (pin "20") (pinfunction "PC5_20") (pintype "passive"))
    )
    (net (code "84") (name "unconnected-(Core1-PC6-Pad46)") (class "Default")
      (node (ref "Core1") (pin "46") (pinfunction "PC6_46") (pintype "passive"))
    )
    (net (code "85") (name "unconnected-(Core1-PC9-Pad43)") (class "Default")
      (node (ref "Core1") (pin "43") (pinfunction "PC9_43") (pintype "passive"))
    )
    (net (code "86") (name "unconnected-(Core1-PC10-Pad34)") (class "Default")
      (node (ref "Core1") (pin "34") (pinfunction "PC10_34") (pintype "passive"))
    )
    (net (code "87") (name "unconnected-(Core1-PD2-Pad33)") (class "Default")
      (node (ref "Core1") (pin "33") (pinfunction "PD2_33") (pintype "passive"))
    )
    (net (code "88") (name "unconnected-(P1-Pad2)") (class "Default")
      (node (ref "P1") (pin "2") (pinfunction "2_2") (pintype "passive"))
    )
    (net (code "89") (name "unconnected-(P1-Pad4)") (class "Default")
      (node (ref "P1") (pin "4") (pinfunction "4_4") (pintype "passive"))
    )
    (net (code "90") (name "unconnected-(P1-Pad5)") (class "Default")
      (node (ref "P1") (pin "5") (pinfunction "5_5") (pintype "passive"))
    )
    (net (code "91") (name "unconnected-(TJA1-Vref-Pad5)") (class "Default")
      (node (ref "TJA1") (pin "5") (pinfunction "Vref_5") (pintype "passive"))
    )
    (net (code "92") (name "unconnected-(TPS1-ENA-Pad5)") (class "Default")
      (node (ref "TPS1") (pin "5") (pinfunction "ENA_5") (pintype "passive"))
    )
    (net (code "93") (name "unconnected-(TPS1-NC-Pad2)") (class "Default")
      (node (ref "TPS1") (pin "2") (pinfunction "NC_2") (pintype "passive"))
    )
    (net (code "94") (name "unconnected-(TPS1-NC-Pad3)") (class "Default")
      (node (ref "TPS1") (pin "3") (pinfunction "NC_3") (pintype "passive"))
    )
    (net (code "95") (name "unconnected-(U2-TAB-Pad4)") (class "Default")
      (node (ref "U2") (pin "4") (pinfunction "TAB_4") (pintype "power_in"))
    )
  )
)
